# eeZeeAmpJig.net
KiCad netlist of a schematic drawn in EAGLE
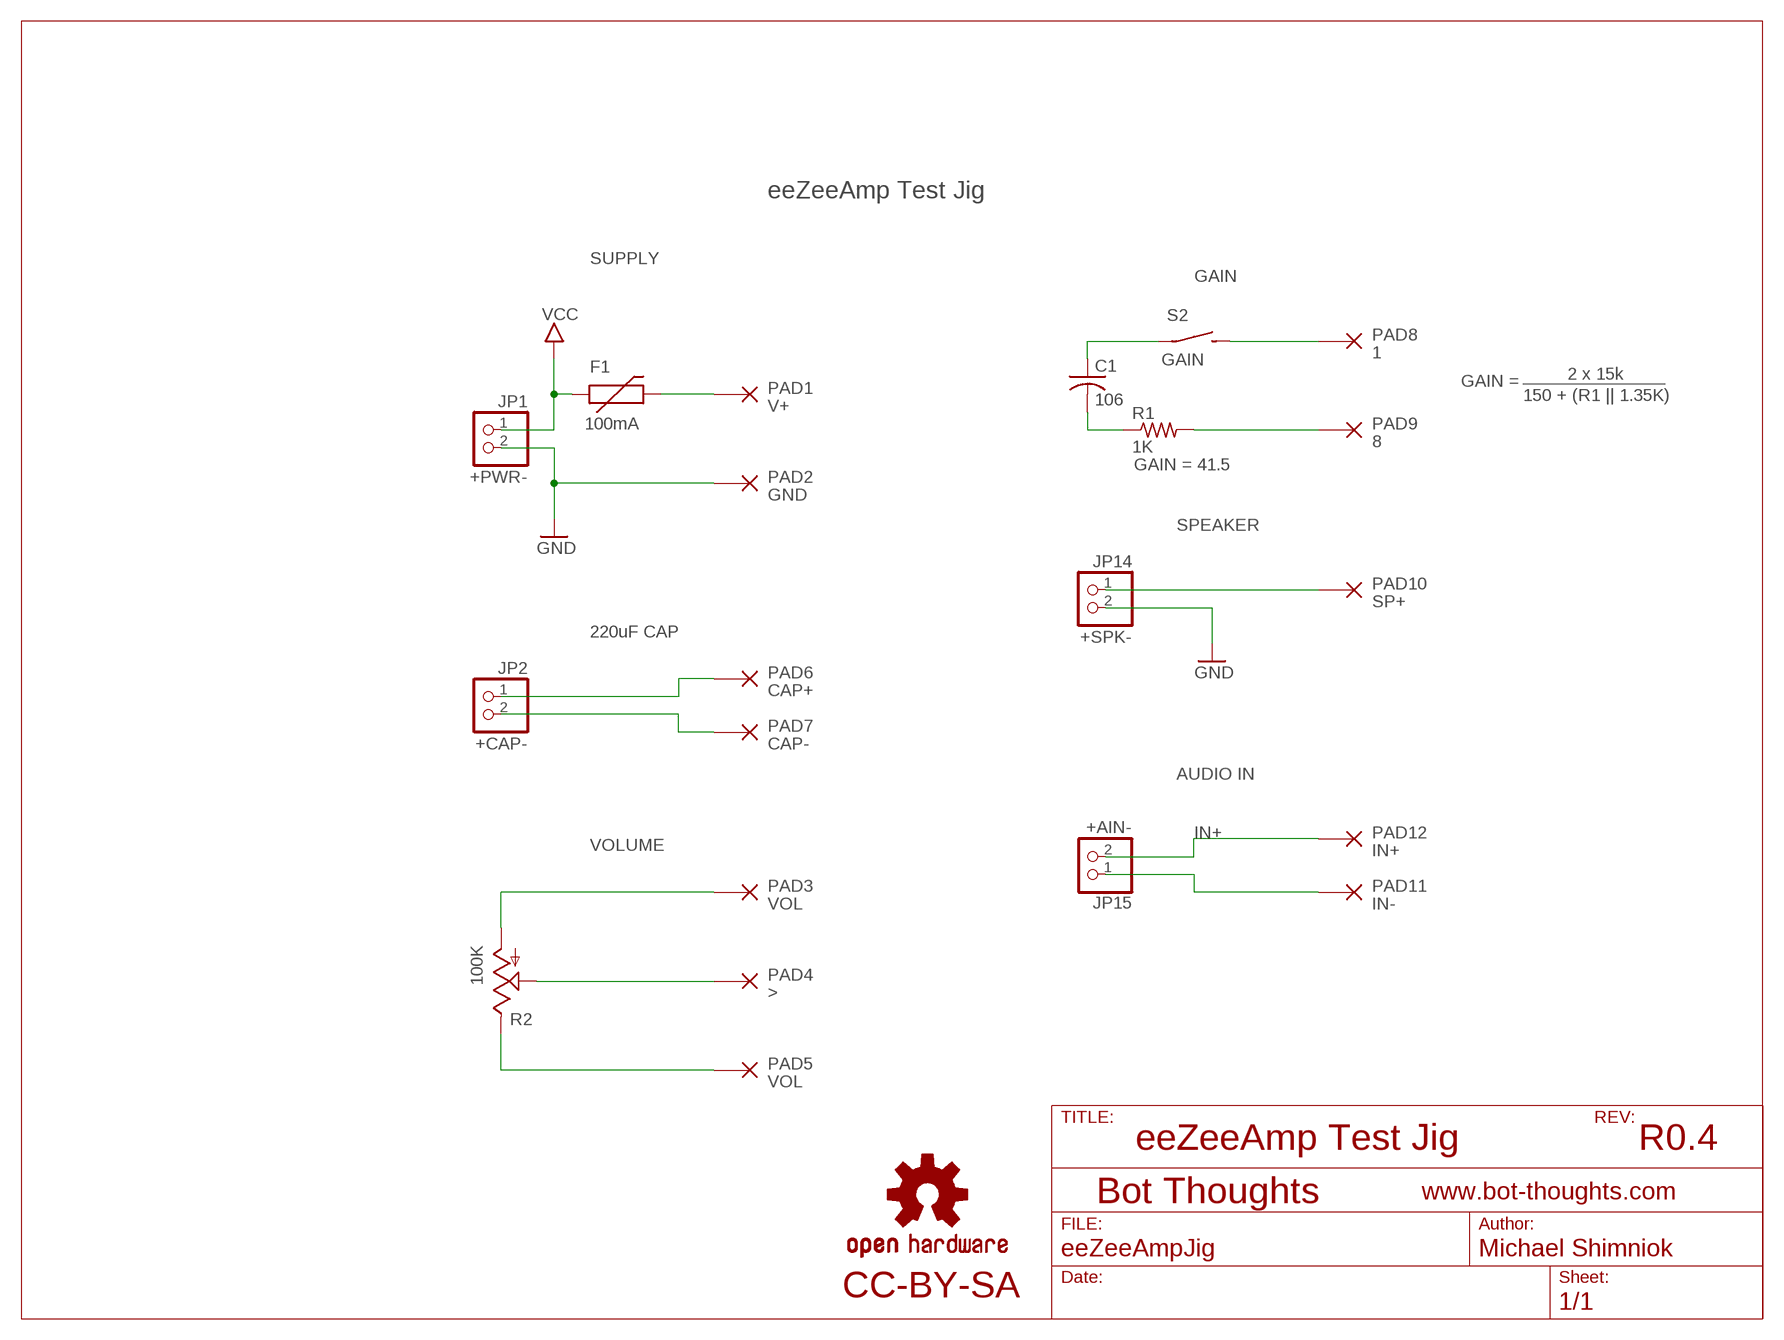
[diagram p0: schematic, sheet 1]

(export (version "E")
  (design (tool "Eeschema 10.0.6"))
  (components
    (comp (ref "C1")
      (value "106")
      (footprint "eagle-import:C0805")
      (libsource (lib "eagle-import") (part "C-USC0805"))
    )
    (comp (ref "F1")
      (value "100mA")
      (footprint "eagle-import:0603")
      (libsource (lib "eagle-import") (part "PTC0603"))
    )
    (comp (ref "JP1")
      (value "+PWR-")
      (footprint "eagle-import:1X02-S")
      (libsource (lib "eagle-import") (part "PINHD-1X02_2.54-S"))
    )
    (comp (ref "JP2")
      (value "+CAP-")
      (footprint "eagle-import:1X02-S")
      (libsource (lib "eagle-import") (part "PINHD-1X02_2.54-S"))
    )
    (comp (ref "JP14")
      (value "+SPK-")
      (footprint "eagle-import:1X02-S")
      (libsource (lib "eagle-import") (part "PINHD-1X02_2.54-S"))
    )
    (comp (ref "JP15")
      (value "+AIN-")
      (footprint "eagle-import:1X02-S")
      (libsource (lib "eagle-import") (part "PINHD-1X02_2.54-S"))
    )
    (comp (ref "LOGO2")
      (value "OSHW-LOGOS")
      (footprint "eagle-import:OSHW-LOGO-S")
      (libsource (lib "eagle-import") (part "OSHW-LOGOS"))
    )
    (comp (ref "PAD1")
      (value "V+")
      (footprint "eagle-import:POGO_1.02MM")
      (libsource (lib "eagle-import") (part "WIREPAD_1.2MM"))
    )
    (comp (ref "PAD2")
      (value "GND")
      (footprint "eagle-import:POGO_1.02MM")
      (libsource (lib "eagle-import") (part "WIREPAD_1.2MM"))
    )
    (comp (ref "PAD3")
      (value "VOL")
      (footprint "eagle-import:POGO_1.02MM")
      (libsource (lib "eagle-import") (part "WIREPAD_1.2MM"))
    )
    (comp (ref "PAD4")
      (value ">")
      (footprint "eagle-import:POGO_1.02MM")
      (libsource (lib "eagle-import") (part "WIREPAD_1.2MM"))
    )
    (comp (ref "PAD5")
      (value "VOL")
      (footprint "eagle-import:POGO_1.02MM")
      (libsource (lib "eagle-import") (part "WIREPAD_1.2MM"))
    )
    (comp (ref "PAD6")
      (value "CAP+")
      (footprint "eagle-import:POGO_1.02MM")
      (libsource (lib "eagle-import") (part "WIREPAD_1.2MM"))
    )
    (comp (ref "PAD7")
      (value "CAP-")
      (footprint "eagle-import:POGO_1.02MM")
      (libsource (lib "eagle-import") (part "WIREPAD_1.2MM"))
    )
    (comp (ref "PAD8")
      (value "1")
      (footprint "eagle-import:POGO_1.02MM")
      (libsource (lib "eagle-import") (part "WIREPAD_1.2MM"))
    )
    (comp (ref "PAD9")
      (value "8")
      (footprint "eagle-import:POGO_1.02MM")
      (libsource (lib "eagle-import") (part "WIREPAD_1.2MM"))
    )
    (comp (ref "PAD10")
      (value "SP+")
      (footprint "eagle-import:POGO_1.02MM")
      (libsource (lib "eagle-import") (part "WIREPAD_1.2MM"))
    )
    (comp (ref "PAD11")
      (value "IN-")
      (footprint "eagle-import:POGO_1.02MM")
      (libsource (lib "eagle-import") (part "WIREPAD_1.2MM"))
    )
    (comp (ref "PAD12")
      (value "IN+")
      (footprint "eagle-import:POGO_1.02MM")
      (libsource (lib "eagle-import") (part "WIREPAD_1.2MM"))
    )
    (comp (ref "R1")
      (value "1K")
      (footprint "eagle-import:R0603")
      (libsource (lib "eagle-import") (part "R-US_R0603"))
    )
    (comp (ref "R2")
      (value "100K")
      (footprint "eagle-import:CA6H")
      (libsource (lib "eagle-import") (part "TRIM_US-CA6H"))
    )
    (comp (ref "S2")
      (value "GAIN")
      (footprint "eagle-import:3X4X2TACT")
      (libsource (lib "eagle-import") (part "SPST_3X4X2"))
    )
  )
  (nets
    (net (code "1") (name "/IN+") (class "Default")
      (node (ref "JP15") (pin "2") (pinfunction "2_2") (pintype "passive"))
      (node (ref "PAD12") (pin "P$1") (pinfunction "P_P$1") (pintype "bidirectional"))
    )
    (net (code "2") (name "GND") (class "Default")
      (node (ref "JP1") (pin "2") (pinfunction "2_2") (pintype "passive"))
      (node (ref "JP14") (pin "2") (pinfunction "2_2") (pintype "passive"))
      (node (ref "PAD2") (pin "P$1") (pinfunction "P_P$1") (pintype "bidirectional"))
    )
    (net (code "3") (name "Net-(C1-Pad2)") (class "Default")
      (node (ref "C1") (pin "2") (pinfunction "2_2") (pintype "passive"))
      (node (ref "R1") (pin "1") (pinfunction "1_1") (pintype "passive"))
    )
    (net (code "4") (name "Net-(PAD1-P)") (class "Default")
      (node (ref "F1") (pin "2") (pinfunction "2_2") (pintype "bidirectional"))
      (node (ref "PAD1") (pin "P$1") (pinfunction "P_P$1") (pintype "bidirectional"))
    )
    (net (code "5") (name "Net-(PAD3-P)") (class "Default")
      (node (ref "PAD3") (pin "P$1") (pinfunction "P_P$1") (pintype "bidirectional"))
      (node (ref "R2") (pin "A") (pinfunction "A_A") (pintype "passive"))
    )
    (net (code "6") (name "Net-(PAD4-P)") (class "Default")
      (node (ref "PAD4") (pin "P$1") (pinfunction "P_P$1") (pintype "bidirectional"))
      (node (ref "R2") (pin "S") (pinfunction "S_S") (pintype "passive"))
    )
    (net (code "7") (name "Net-(PAD5-P)") (class "Default")
      (node (ref "PAD5") (pin "P$1") (pinfunction "P_P$1") (pintype "bidirectional"))
      (node (ref "R2") (pin "E") (pinfunction "E_E") (pintype "passive"))
    )
    (net (code "8") (name "Net-(PAD6-P)") (class "Default")
      (node (ref "JP2") (pin "1") (pinfunction "1_1") (pintype "passive"))
      (node (ref "PAD6") (pin "P$1") (pinfunction "P_P$1") (pintype "bidirectional"))
    )
    (net (code "9") (name "Net-(PAD7-P)") (class "Default")
      (node (ref "JP2") (pin "2") (pinfunction "2_2") (pintype "passive"))
      (node (ref "PAD7") (pin "P$1") (pinfunction "P_P$1") (pintype "bidirectional"))
    )
    (net (code "10") (name "Net-(PAD8-P)") (class "Default")
      (node (ref "PAD8") (pin "P$1") (pinfunction "P_P$1") (pintype "bidirectional"))
      (node (ref "S2") (pin "P$2") (pinfunction "S_P$2") (pintype "passive"))
    )
    (net (code "11") (name "Net-(PAD9-P)") (class "Default")
      (node (ref "PAD9") (pin "P$1") (pinfunction "P_P$1") (pintype "bidirectional"))
      (node (ref "R1") (pin "2") (pinfunction "2_2") (pintype "passive"))
    )
    (net (code "12") (name "Net-(PAD10-P)") (class "Default")
      (node (ref "JP14") (pin "1") (pinfunction "1_1") (pintype "passive"))
      (node (ref "PAD10") (pin "P$1") (pinfunction "P_P$1") (pintype "bidirectional"))
    )
    (net (code "13") (name "Net-(PAD11-P)") (class "Default")
      (node (ref "JP15") (pin "1") (pinfunction "1_1") (pintype "passive"))
      (node (ref "PAD11") (pin "P$1") (pinfunction "P_P$1") (pintype "bidirectional"))
    )
    (net (code "14") (name "Net-(S2-P)") (class "Default")
      (node (ref "C1") (pin "1") (pinfunction "1_1") (pintype "passive"))
      (node (ref "S2") (pin "P$1") (pinfunction "P_P$1") (pintype "passive"))
    )
    (net (code "15") (name "VCC") (class "Default")
      (node (ref "F1") (pin "1") (pinfunction "1_1") (pintype "bidirectional"))
      (node (ref "JP1") (pin "1") (pinfunction "1_1") (pintype "passive"))
    )
  )
)
